# 01_-_CC2650.net
KiCad netlist of a schematic drawn in Altium Designer
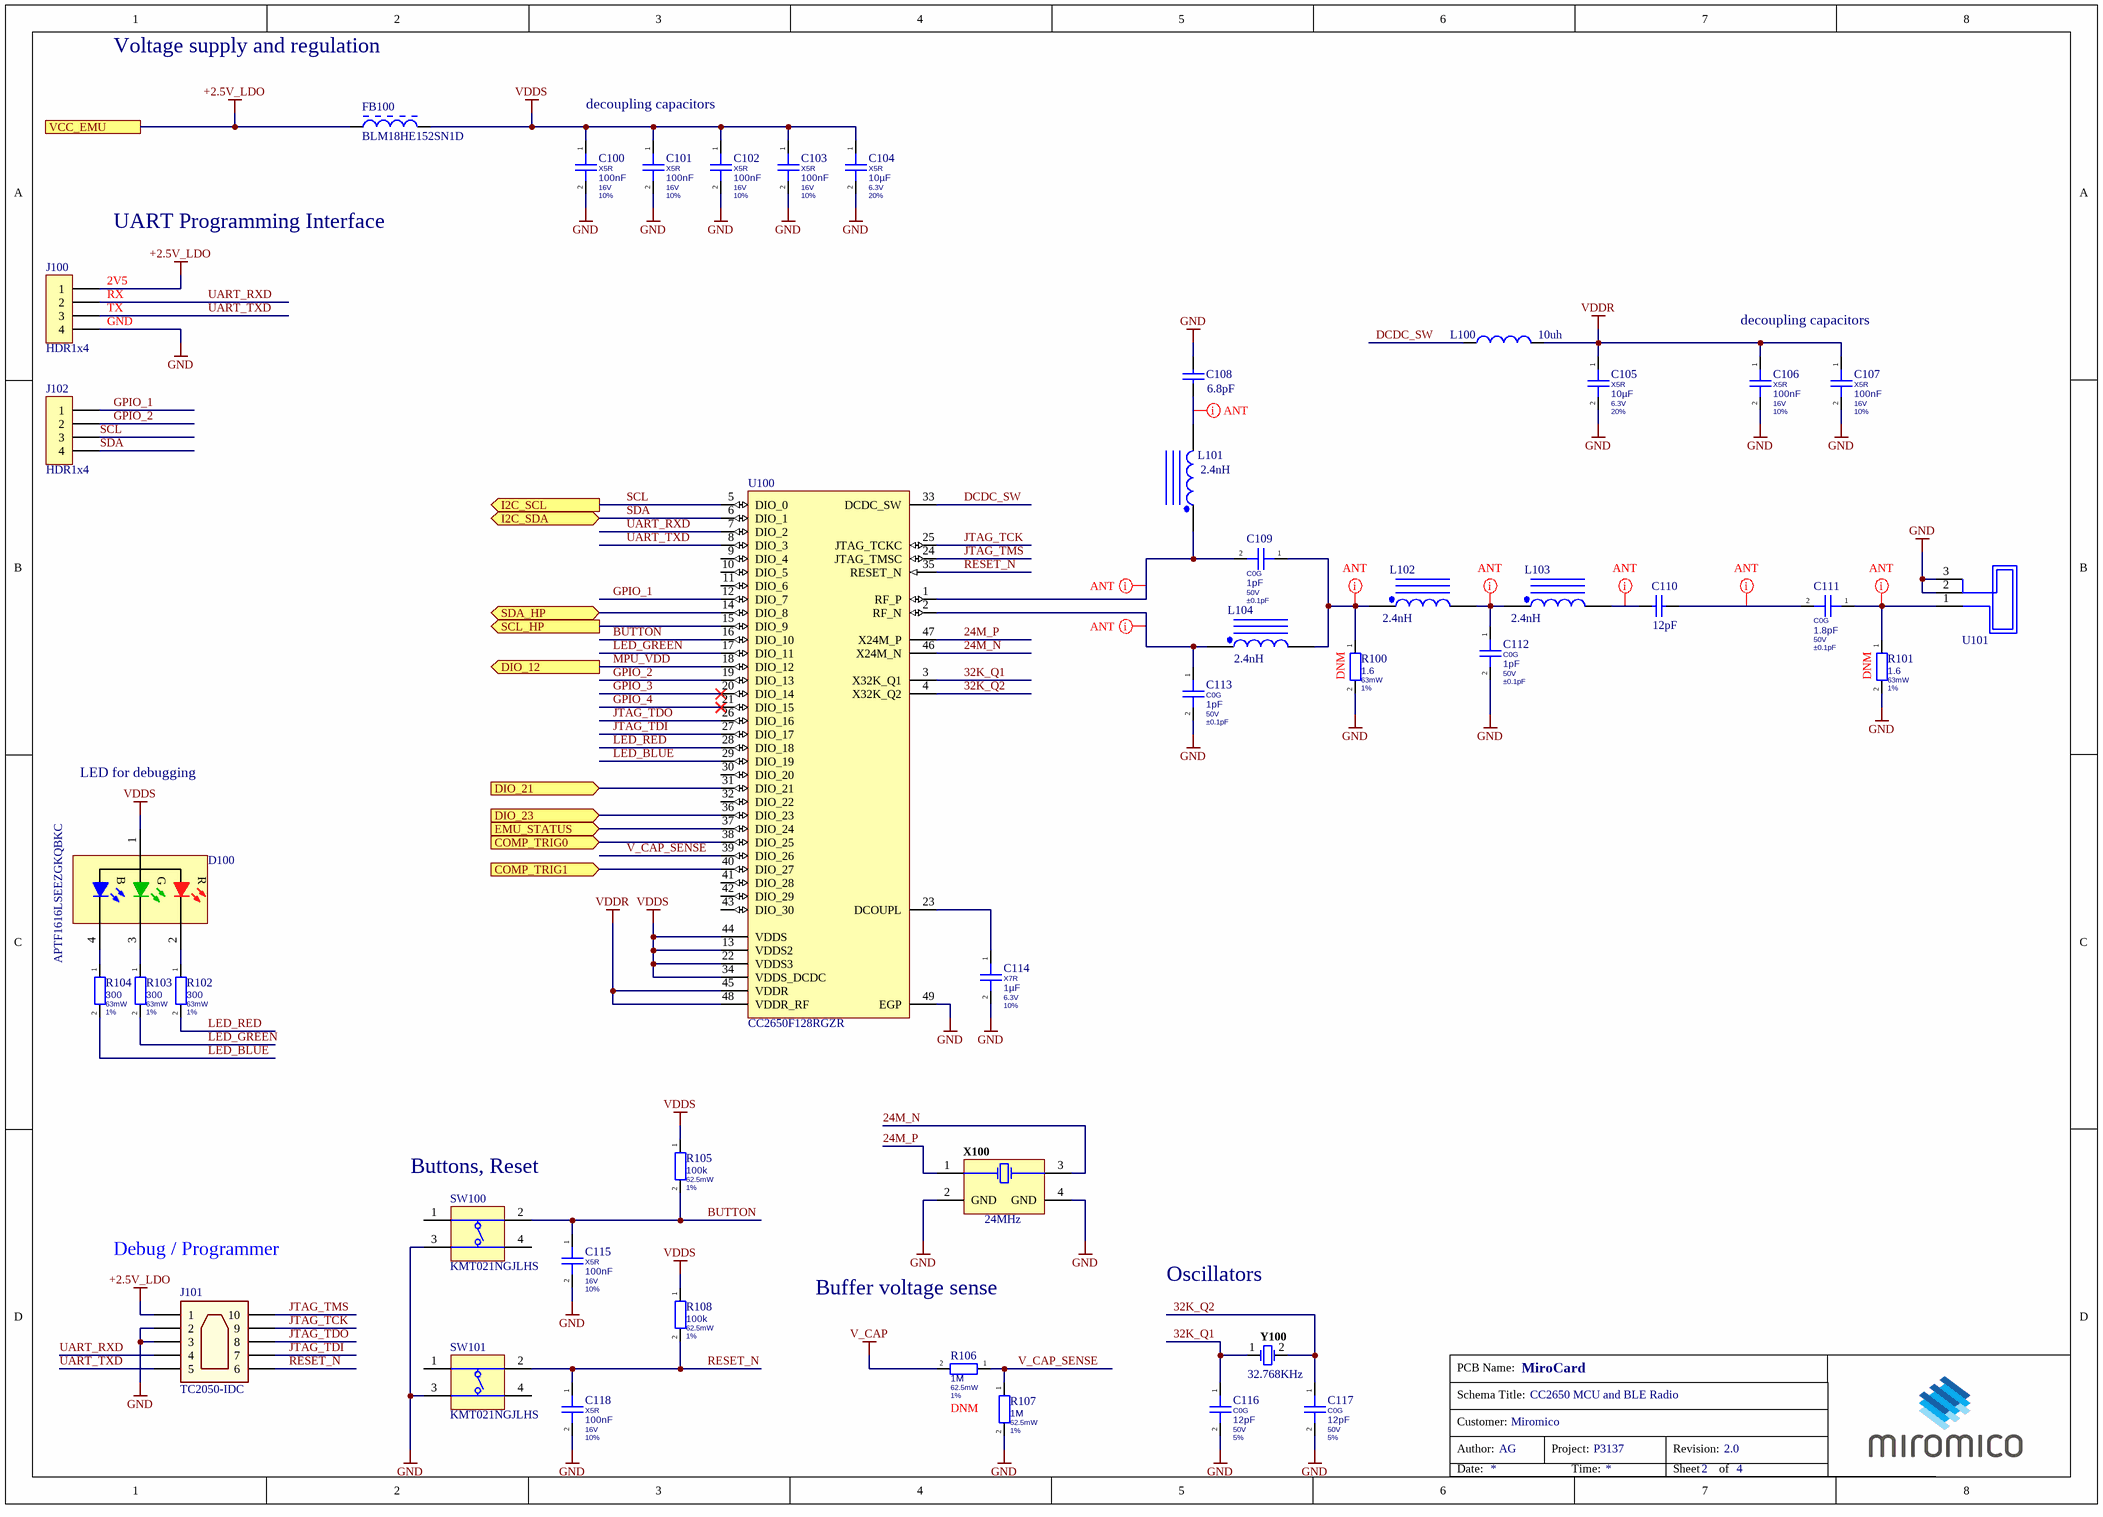
[diagram p0: 01 - CC2650.SchDoc]

(export (version "E")
  (design (tool "Eeschema 10.0.6"))
  (components
    (comp (ref "C100")
      (value "GRM155R61C104KA88D")
      (footprint "CAPC0402(1005)60_L")
      (description "0.1µF ±10% 16V Ceramic Capacitor X5R 0402 (1005 Metric)")
      (fields
        (field (name "DIELECTRIC") "X5R")
        (field (name "CAPACITANCE") "100nF")
        (field (name "VOLTAGE RATING") "16V")
        (field (name "TOLERANCE") "10%")
        (field (name "MANUFACTURER") "Murata Electronics")
        (field (name "VOLTAGE") "16V")
      )
      (libsource (lib "Altium Vault Miromico") (part "=Capacitance"))
    )
    (comp (ref "C101")
      (value "GRM155R61C104KA88D")
      (footprint "CAPC0402(1005)60_L")
      (description "0.1µF ±10% 16V Ceramic Capacitor X5R 0402 (1005 Metric)")
      (fields
        (field (name "DIELECTRIC") "X5R")
        (field (name "CAPACITANCE") "100nF")
        (field (name "VOLTAGE RATING") "16V")
        (field (name "TOLERANCE") "10%")
        (field (name "MANUFACTURER") "Murata Electronics")
        (field (name "VOLTAGE") "16V")
      )
      (libsource (lib "Altium Vault Miromico") (part "=Capacitance"))
    )
    (comp (ref "C102")
      (value "GRM155R61C104KA88D")
      (footprint "CAPC0402(1005)60_L")
      (description "0.1µF ±10% 16V Ceramic Capacitor X5R 0402 (1005 Metric)")
      (fields
        (field (name "DIELECTRIC") "X5R")
        (field (name "CAPACITANCE") "100nF")
        (field (name "VOLTAGE RATING") "16V")
        (field (name "TOLERANCE") "10%")
        (field (name "MANUFACTURER") "Murata Electronics")
        (field (name "VOLTAGE") "16V")
      )
      (libsource (lib "Altium Vault Miromico") (part "=Capacitance"))
    )
    (comp (ref "C103")
      (value "GRM155R61C104KA88D")
      (footprint "CAPC0402(1005)60_L")
      (description "0.1µF ±10% 16V Ceramic Capacitor X5R 0402 (1005 Metric)")
      (fields
        (field (name "DIELECTRIC") "X5R")
        (field (name "CAPACITANCE") "100nF")
        (field (name "VOLTAGE RATING") "16V")
        (field (name "TOLERANCE") "10%")
        (field (name "MANUFACTURER") "Murata Electronics")
        (field (name "VOLTAGE") "16V")
      )
      (libsource (lib "Altium Vault Miromico") (part "=Capacitance"))
    )
    (comp (ref "C104")
      (value "GRJ155R60J106ME11D")
      (footprint "CAPC0402(1005)60_L")
      (description "10µF ±20% 6.3V Ceramic Capacitor X5R 0402 (1005 Metric)")
      (fields
        (field (name "DIELECTRIC") "X5R")
        (field (name "CAPACITANCE") "10µF")
        (field (name "VOLTAGE RATING") "6.3V")
        (field (name "TOLERANCE") "20%")
        (field (name "MANUFACTURER") "Murata Electronics")
      )
      (libsource (lib "Altium Vault Miromico") (part "=Capacitance"))
    )
    (comp (ref "C105")
      (value "GRJ155R60J106ME11D")
      (footprint "CAPC0402(1005)60_L")
      (description "10µF ±20% 6.3V Ceramic Capacitor X5R 0402 (1005 Metric)")
      (fields
        (field (name "DIELECTRIC") "X5R")
        (field (name "CAPACITANCE") "10µF")
        (field (name "VOLTAGE RATING") "6.3V")
        (field (name "TOLERANCE") "20%")
        (field (name "MANUFACTURER") "Murata Electronics")
      )
      (libsource (lib "Altium Vault Miromico") (part "=Capacitance"))
    )
    (comp (ref "C106")
      (value "GRM155R61C104KA88D")
      (footprint "CAPC0402(1005)60_L")
      (description "0.1µF ±10% 16V Ceramic Capacitor X5R 0402 (1005 Metric)")
      (fields
        (field (name "DIELECTRIC") "X5R")
        (field (name "CAPACITANCE") "100nF")
        (field (name "VOLTAGE RATING") "16V")
        (field (name "TOLERANCE") "10%")
        (field (name "MANUFACTURER") "Murata Electronics")
        (field (name "VOLTAGE") "16V")
      )
      (libsource (lib "Altium Vault Miromico") (part "=Capacitance"))
    )
    (comp (ref "C107")
      (value "GRM155R61C104KA88D")
      (footprint "CAPC0402(1005)60_L")
      (description "0.1µF ±10% 16V Ceramic Capacitor X5R 0402 (1005 Metric)")
      (fields
        (field (name "DIELECTRIC") "X5R")
        (field (name "CAPACITANCE") "100nF")
        (field (name "VOLTAGE RATING") "16V")
        (field (name "TOLERANCE") "10%")
        (field (name "MANUFACTURER") "Murata Electronics")
        (field (name "VOLTAGE") "16V")
      )
      (libsource (lib "Altium Vault Miromico") (part "=Capacitance"))
    )
    (comp (ref "C108")
      (value "6.8pF")
      (footprint "CAPC0402(1005)60_L")
      (description "CAP 6.8pF 10V ±5% 0402 (1005 Metric) Thickness 0.6mm SMD")
      (fields (field (name "TOLERANCE") "Â±5%") (field (name "Comment") "CAP 6.8pF 10V 0402(1005)"))
      (libsource (lib "Altium Content Vault") (part "CMP-1034-00503-1"))
    )
    (comp (ref "C109")
      (value "GRM1555C1H1R0BA01D")
      (footprint "CAPC0402(1005)60_L")
      (description "1pF ±0.1pF 50V Ceramic Capacitor C0G, NP0 0402 (1005 Metric)")
      (fields
        (field (name "DIELECTRIC") "C0G")
        (field (name "CAPACITANCE") "1pF")
        (field (name "VOLTAGE RATING") "50V")
        (field (name "TOLERANCE") "±0.1pF")
        (field (name "MANUFACTURER") "Murata Electronics")
        (field (name "VOLTAGE") "50V")
      )
      (libsource (lib "Altium Vault Miromico") (part "=Capacitance"))
    )
    (comp (ref "C110")
      (value "12pF")
      (footprint "CAPC0402(1005)60_L")
      (description "CAP 12pF 10V ±2% 0402 (1005 Metric) Thickness 0.6mm SMD")
      (fields (field (name "TOLERANCE") "Â±2%") (field (name "Comment") "CAP 12pF 10V 0402(1005)"))
      (libsource (lib "Altium Content Vault") (part "CMP-1034-00750-1"))
    )
    (comp (ref "C111")
      (value "GRM1555C1H1R8BA01D")
      (footprint "CAPC0402(1005)60_L")
      (description "1.8pF ±0.1pF 50V Ceramic Capacitor C0G, NP0 0402 (1005 Metric)")
      (fields
        (field (name "DIELECTRIC") "C0G")
        (field (name "CAPACITANCE") "1.8pF")
        (field (name "VOLTAGE RATING") "50V")
        (field (name "TOLERANCE") "±0.1pF")
        (field (name "VOLTAGE") "50V")
        (field (name "MANUFACTURER") "Murata Electronics")
      )
      (libsource (lib "Altium Vault Miromico") (part "=Capacitance"))
    )
    (comp (ref "C112")
      (value "GRM1555C1H1R0BA01D")
      (footprint "CAPC0402(1005)60_L")
      (description "1pF ±0.1pF 50V Ceramic Capacitor C0G, NP0 0402 (1005 Metric)")
      (fields
        (field (name "DIELECTRIC") "C0G")
        (field (name "CAPACITANCE") "1pF")
        (field (name "VOLTAGE RATING") "50V")
        (field (name "TOLERANCE") "±0.1pF")
        (field (name "MANUFACTURER") "Murata Electronics")
        (field (name "VOLTAGE") "50V")
      )
      (libsource (lib "Altium Vault Miromico") (part "=Capacitance"))
    )
    (comp (ref "C113")
      (value "GRM1555C1H1R0BA01D")
      (footprint "CAPC0402(1005)60_L")
      (description "1pF ±0.1pF 50V Ceramic Capacitor C0G, NP0 0402 (1005 Metric)")
      (fields
        (field (name "DIELECTRIC") "C0G")
        (field (name "CAPACITANCE") "1pF")
        (field (name "VOLTAGE RATING") "50V")
        (field (name "TOLERANCE") "±0.1pF")
        (field (name "MANUFACTURER") "Murata Electronics")
        (field (name "VOLTAGE") "50V")
      )
      (libsource (lib "Altium Vault Miromico") (part "=Capacitance"))
    )
    (comp (ref "C114")
      (value "GRM155R70J105KA12J")
      (footprint "CAPC0402(1005)60_L")
      (description "1µF ±10% 6.3V Ceramic Capacitor X7R 0402 (1005 Metric)")
      (fields
        (field (name "DIELECTRIC") "X7R")
        (field (name "CAPACITANCE") "1µF")
        (field (name "VOLTAGE RATING") "6.3V")
        (field (name "TOLERANCE") "10%")
        (field (name "MANUFACTURER") "Murata Electronics")
      )
      (libsource (lib "Altium Vault Miromico") (part "=Capacitance"))
    )
    (comp (ref "C115")
      (value "GRM155R61C104KA88D")
      (footprint "CAPC0402(1005)60_L")
      (description "0.1µF ±10% 16V Ceramic Capacitor X5R 0402 (1005 Metric)")
      (fields
        (field (name "DIELECTRIC") "X5R")
        (field (name "CAPACITANCE") "100nF")
        (field (name "VOLTAGE RATING") "16V")
        (field (name "TOLERANCE") "10%")
        (field (name "MANUFACTURER") "Murata Electronics")
        (field (name "VOLTAGE") "16V")
      )
      (libsource (lib "Altium Vault Miromico") (part "=Capacitance"))
    )
    (comp (ref "C116")
      (value "GRM1555C1H120JA01D")
      (footprint "CAPC0402(1005)60_L")
      (description "12pF ±5% 50V Ceramic Capacitor C0G, NP0 0402 (1005 Metric)")
      (fields
        (field (name "DIELECTRIC") "C0G")
        (field (name "CAPACITANCE") "12pF")
        (field (name "VOLTAGE RATING") "50V")
        (field (name "TOLERANCE") "5%")
        (field (name "MANUFACTURER") "Murata Electronics")
        (field (name "VOLTAGE") "50V")
      )
      (libsource (lib "Altium Vault Miromico") (part "=Capacitance"))
    )
    (comp (ref "C117")
      (value "GRM1555C1H120JA01D")
      (footprint "CAPC0402(1005)60_L")
      (description "12pF ±5% 50V Ceramic Capacitor C0G, NP0 0402 (1005 Metric)")
      (fields
        (field (name "DIELECTRIC") "C0G")
        (field (name "CAPACITANCE") "12pF")
        (field (name "VOLTAGE RATING") "50V")
        (field (name "TOLERANCE") "5%")
        (field (name "MANUFACTURER") "Murata Electronics")
        (field (name "VOLTAGE") "50V")
      )
      (libsource (lib "Altium Vault Miromico") (part "=Capacitance"))
    )
    (comp (ref "C118")
      (value "GRM155R61C104KA88D")
      (footprint "CAPC0402(1005)60_L")
      (description "0.1µF ±10% 16V Ceramic Capacitor X5R 0402 (1005 Metric)")
      (fields
        (field (name "DIELECTRIC") "X5R")
        (field (name "CAPACITANCE") "100nF")
        (field (name "VOLTAGE RATING") "16V")
        (field (name "TOLERANCE") "10%")
        (field (name "MANUFACTURER") "Murata Electronics")
        (field (name "VOLTAGE") "16V")
      )
      (libsource (lib "Altium Vault Miromico") (part "=Capacitance"))
    )
    (comp (ref "D100")
      (value "APTF1616LSEEZGKQBKC")
      (footprint "APTF1616LSEEZGKQBKC")
      (description "HELI Colour; 1.6X1.6MM LOW CURRENT RGB SMD LED")
      (fields (field (name "MANUFACTURER") "Kingbright"))
      (libsource (lib "Altium Vault Miromico") (part "APTF1616LSEEZGKQBKC"))
    )
    (comp (ref "FB100")
      (value "BLM18HE152SN1D")
      (footprint "MURA-BLM18-RF-H4-CHIP-2_V")
      (fields (field (name "MANUFACTURER") "Murata"))
      (libsource (lib "Altium Content Vault") (part "MURA-FB-2"))
    )
    (comp (ref "J100")
      (value "HDR1x4")
      (footprint "HDR1x4")
      (description "1x4 Pin Header, 2.54mm")
      (libsource (lib "Altium Vault Miromico") (part "HDR1x4"))
    )
    (comp (ref "J101")
      (value "TC2050-IDC")
      (footprint "TC2050-IDC-NL-10")
      (description "TDC2050-IDC, 10Pins, dual footprint (leg and no-legs)")
      (fields (field (name "MANUFACTURER") "Tag-Connect"))
      (libsource (lib "Altium Vault Miromico") (part "TDC2050-IDC-03"))
    )
    (comp (ref "J102")
      (value "HDR1x4")
      (footprint "HDR1x4")
      (description "1x4 Pin Header, 2.54mm")
      (libsource (lib "Altium Vault Miromico") (part "HDR1x4"))
    )
    (comp (ref "L100")
      (value "CKS2125100M-T")
      (footprint "INDC0805(2012)X11_L")
      (description "FIXED IND 10UH 110MA 520 MOHM")
      (fields (field (name "TOLERANCE") "20%") (field (name "INDUCTANCE") "10uh"))
      (libsource (lib "TransientBLE") (part "CMP-00871-1"))
    )
    (comp (ref "L101")
      (value "LQG15HS2N4S02D")
      (footprint "INDC1005X55X25LL05T10_A")
      (fields
        (field (name "INDUCTANCE") "2.4nH")
        (field (name "MANUFACTURER") "MurataElectronics")
        (field (name "TOLERANCE") "0.3nH")
      )
      (libsource (lib "Altium Content Vault") (part "CMP-2000-06579-1"))
    )
    (comp (ref "L102")
      (value "LQG15HS2N4S02D")
      (footprint "INDC1005X55X25LL05T10_A")
      (fields
        (field (name "INDUCTANCE") "2.4nH")
        (field (name "MANUFACTURER") "MurataElectronics")
        (field (name "TOLERANCE") "0.3nH")
      )
      (libsource (lib "Altium Content Vault") (part "CMP-2000-06579-1"))
    )
    (comp (ref "L103")
      (value "LQG15HS2N4S02D")
      (footprint "INDC1005X55X25LL05T10_A")
      (fields
        (field (name "INDUCTANCE") "2.4nH")
        (field (name "MANUFACTURER") "MurataElectronics")
        (field (name "TOLERANCE") "0.3nH")
      )
      (libsource (lib "Altium Content Vault") (part "CMP-2000-06579-1"))
    )
    (comp (ref "L104")
      (value "LQG15HS2N4S02D")
      (footprint "INDC1005X55X25LL05T10_A")
      (fields
        (field (name "INDUCTANCE") "2.4nH")
        (field (name "MANUFACTURER") "MurataElectronics")
        (field (name "TOLERANCE") "0.3nH")
      )
      (libsource (lib "Altium Content Vault") (part "CMP-2000-06579-1"))
    )
    (comp (ref "R100")
      (value "CRCW04021R60FKED")
      (footprint "RESC0402(1005)_L")
      (description "1.6 Ohms ±1% 0.063W, 1/16W Chip Resistor 0402 (1005 Metric) Automotive AEC-Q200 Thick Film")
      (fields
        (field (name "RESISTANCE") "1.6")
        (field (name "POWER RATING") "63mW")
        (field (name "TOLERANCE") "1%")
        (field (name "MANUFACTURER") "Vishay Dale")
      )
      (libsource (lib "") (part "=Resistance_1"))
    )
    (comp (ref "R101")
      (value "CRCW04021R60FKED")
      (footprint "RESC0402(1005)_L")
      (description "1.6 Ohms ±1% 0.063W, 1/16W Chip Resistor 0402 (1005 Metric) Automotive AEC-Q200 Thick Film")
      (fields
        (field (name "RESISTANCE") "1.6")
        (field (name "POWER RATING") "63mW")
        (field (name "TOLERANCE") "1%")
        (field (name "MANUFACTURER") "Vishay Dale")
      )
      (libsource (lib "") (part "=Resistance_1"))
    )
    (comp (ref "R102")
      (value "RMCF0402FT300R")
      (footprint "RESC0402(1005)_L")
      (fields
        (field (name "RESISTANCE") "300")
        (field (name "POWER RATING") "63mW")
        (field (name "TOLERANCE") "1%")
        (field (name "MANUFACTURER") "Stackpole Electronics Inc")
      )
      (libsource (lib "") (part "=Resistance_1"))
    )
    (comp (ref "R103")
      (value "RMCF0402FT300R")
      (footprint "RESC0402(1005)_L")
      (fields
        (field (name "RESISTANCE") "300")
        (field (name "POWER RATING") "63mW")
        (field (name "TOLERANCE") "1%")
        (field (name "MANUFACTURER") "Stackpole Electronics Inc")
      )
      (libsource (lib "") (part "=Resistance_1"))
    )
    (comp (ref "R104")
      (value "RMCF0402FT300R")
      (footprint "RESC0402(1005)_L")
      (fields
        (field (name "RESISTANCE") "300")
        (field (name "POWER RATING") "63mW")
        (field (name "TOLERANCE") "1%")
        (field (name "MANUFACTURER") "Stackpole Electronics Inc")
      )
      (libsource (lib "") (part "=Resistance_1"))
    )
    (comp (ref "R105")
      (value "RMCF0402FT100K")
      (footprint "RESC0402(1005)_L")
      (fields
        (field (name "RESISTANCE") "100k")
        (field (name "POWER RATING") "62.5mW")
        (field (name "TOLERANCE") "1%")
        (field (name "MANUFACTURER") "Stackpole Electronics Inc")
      )
      (libsource (lib "") (part "=Resistance_1"))
    )
    (comp (ref "R106")
      (value "RMCF0402FT1M00")
      (footprint "RESC0402(1005)_L")
      (fields
        (field (name "RESISTANCE") "1M")
        (field (name "POWER RATING") "62.5mW")
        (field (name "TOLERANCE") "1%")
        (field (name "MANUFACTURER") "Stackpole Electronics Inc")
      )
      (libsource (lib "Altium Vault Miromico") (part "=Resistance"))
    )
    (comp (ref "R107")
      (value "RMCF0402FT1M00")
      (footprint "RESC0402(1005)_L")
      (fields
        (field (name "RESISTANCE") "1M")
        (field (name "POWER RATING") "62.5mW")
        (field (name "TOLERANCE") "1%")
        (field (name "MANUFACTURER") "Stackpole Electronics Inc")
      )
      (libsource (lib "") (part "=Resistance_1"))
    )
    (comp (ref "R108")
      (value "RMCF0402FT100K")
      (footprint "RESC0402(1005)_L")
      (fields
        (field (name "RESISTANCE") "100k")
        (field (name "POWER RATING") "62.5mW")
        (field (name "TOLERANCE") "1%")
        (field (name "MANUFACTURER") "Stackpole Electronics Inc")
      )
      (libsource (lib "") (part "=Resistance_1"))
    )
    (comp (ref "SW100")
      (value "KMT021NGJLHS")
      (footprint "KMT021NGJLHS-Footprint-1")
      (description "Sensorschalter Ultra-LW Tact SW SMT SPNOFa 1.6N HF")
      (fields (field (name "MANUFACTURER") "C&K"))
      (libsource (lib "Altium Vault Miromico") (part "KMT021NGJLHS"))
    )
    (comp (ref "SW101")
      (value "KMT021NGJLHS")
      (footprint "KMT021NGJLHS-Footprint-1")
      (description "Sensorschalter Ultra-LW Tact SW SMT SPNOFa 1.6N HF")
      (fields (field (name "MANUFACTURER") "C&K"))
      (libsource (lib "Altium Vault Miromico") (part "KMT021NGJLHS"))
    )
    (comp (ref "U100")
      (value "CC2650F128RGZR")
      (footprint "RGZ0048A_V")
      (fields (field (name "MANUFACTURER") "Texas Instruments"))
      (libsource (lib "Altium Content Vault") (part "TI-CC2650-VFQFN-48"))
    )
    (comp (ref "U101")
      (value "Antenna Patch")
      (footprint "2.4GHz Inverted F Antenna")
      (description "2.4GHz Inverted F Antenna")
      (libsource (lib "TransientBLE") (part "CMP-00262-1"))
    )
    (comp (ref "X100")
      (value "TSX-3225 24.0000MF15X-AC3")
      (footprint "EPSON-TSX-3225_V")
      (description "MHz Range Crystal, 24 MHz, -40 to 85 degC, 4-Pin SMD, RoHS, Tape and Reel")
      (fields
        (field (name "TOLERANCE") "10PPM")
        (field (name "FREQUENCY") "24MHz")
        (field (name "MANUFACTURER") "Epson")
      )
      (libsource (lib "Altium Content Vault") (part "CMP-2000-07333-1"))
    )
    (comp (ref "Y100")
      (value "ABS07-120-32.768KHZ-T")
      (footprint "ABRA-ABS07_A_V")
      (description "Tuning Fork Crystal, 32.768 KHz, +/- 20 ppm, -40 to 85 degC, 2-Pin SMD, RoHS, Tape and Reel")
      (fields
        (field (name "FREQUENCY") "32.768KHz")
        (field (name "MANUFACTURER") "Abracon")
        (field (name "TOLERANCE") "20ppm")
      )
      (libsource (lib "Altium Content Vault") (part "CMP-2000-07587-1"))
    )
  )
  (nets
    (net (code "1") (name "+2.5V_LDO") (class "Default")
      (node (ref "FB100") (pin "1") (pinfunction "1_1") (pintype "passive"))
      (node (ref "J100") (pin "1") (pinfunction "1_1") (pintype "passive"))
      (node (ref "J101") (pin "1") (pinfunction "1_1") (pintype "passive"))
    )
    (net (code "2") (name "/24M_N") (class "Default")
      (node (ref "U100") (pin "46") (pinfunction "X24M_N_46") (pintype "passive"))
      (node (ref "X100") (pin "3") (pinfunction "X2_3") (pintype "passive"))
    )
    (net (code "3") (name "/24M_P") (class "Default")
      (node (ref "U100") (pin "47") (pinfunction "X24M_P_47") (pintype "passive"))
      (node (ref "X100") (pin "1") (pinfunction "X1_1") (pintype "passive"))
    )
    (net (code "4") (name "/32K_Q1") (class "Default")
      (node (ref "C116") (pin "1") (pinfunction "1_1") (pintype "passive"))
      (node (ref "U100") (pin "3") (pinfunction "X32K_Q1_3") (pintype "passive"))
      (node (ref "Y100") (pin "1") (pinfunction "1_1") (pintype "passive"))
    )
    (net (code "5") (name "/32K_Q2") (class "Default")
      (node (ref "C117") (pin "1") (pinfunction "1_1") (pintype "passive"))
      (node (ref "U100") (pin "4") (pinfunction "X32K_Q2_4") (pintype "passive"))
      (node (ref "Y100") (pin "2") (pinfunction "2_2") (pintype "passive"))
    )
    (net (code "6") (name "/BUTTON") (class "Default")
      (node (ref "C115") (pin "1") (pinfunction "1_1") (pintype "passive"))
      (node (ref "R105") (pin "2") (pinfunction "2_2") (pintype "passive"))
      (node (ref "SW100") (pin "2") (pinfunction "T2_2") (pintype "passive"))
      (node (ref "U100") (pin "16") (pinfunction "DIO_10_16") (pintype "bidirectional"))
    )
    (net (code "7") (name "/COMP_TRIG0") (class "Default")
      (node (ref "U100") (pin "38") (pinfunction "DIO_25_38") (pintype "bidirectional"))
    )
    (net (code "8") (name "/COMP_TRIG1") (class "Default")
      (node (ref "U100") (pin "40") (pinfunction "DIO_27_40") (pintype "bidirectional"))
    )
    (net (code "9") (name "/DCDC_SW") (class "Default")
      (node (ref "L100") (pin "1") (pinfunction "1_1") (pintype "passive"))
      (node (ref "U100") (pin "33") (pinfunction "DCDC_SW_33") (pintype "power_in"))
    )
    (net (code "10") (name "/DIO_21") (class "Default")
      (node (ref "U100") (pin "31") (pinfunction "DIO_21_31") (pintype "bidirectional"))
    )
    (net (code "11") (name "/DIO_23") (class "Default")
      (node (ref "U100") (pin "36") (pinfunction "DIO_23_36") (pintype "bidirectional"))
    )
    (net (code "12") (name "/EMU_STATUS") (class "Default")
      (node (ref "U100") (pin "37") (pinfunction "DIO_24_37") (pintype "bidirectional"))
    )
    (net (code "13") (name "/GPIO_1") (class "Default")
      (node (ref "J102") (pin "1") (pinfunction "1_1") (pintype "passive"))
      (node (ref "U100") (pin "12") (pinfunction "DIO_7_12") (pintype "bidirectional"))
    )
    (net (code "14") (name "/GPIO_2") (class "Default")
      (node (ref "J102") (pin "2") (pinfunction "2_2") (pintype "passive"))
      (node (ref "U100") (pin "19") (pinfunction "DIO_13_19") (pintype "bidirectional"))
    )
    (net (code "15") (name "/GPIO_3") (class "Default")
      (node (ref "U100") (pin "20") (pinfunction "DIO_14_20") (pintype "bidirectional+no_connect"))
    )
    (net (code "16") (name "/GPIO_4") (class "Default")
      (node (ref "U100") (pin "21") (pinfunction "DIO_15_21") (pintype "bidirectional+no_connect"))
    )
    (net (code "17") (name "/JTAG_TCK") (class "Default")
      (node (ref "J101") (pin "9") (pinfunction "9_9") (pintype "passive"))
      (node (ref "U100") (pin "25") (pinfunction "JTAG_TCKC_25") (pintype "bidirectional"))
    )
    (net (code "18") (name "/JTAG_TDI") (class "Default")
      (node (ref "J101") (pin "7") (pinfunction "7_7") (pintype "passive"))
      (node (ref "U100") (pin "27") (pinfunction "DIO_17_27") (pintype "bidirectional"))
    )
    (net (code "19") (name "/JTAG_TDO") (class "Default")
      (node (ref "J101") (pin "8") (pinfunction "8_8") (pintype "passive"))
      (node (ref "U100") (pin "26") (pinfunction "DIO_16_26") (pintype "bidirectional"))
    )
    (net (code "20") (name "/JTAG_TMS") (class "Default")
      (node (ref "J101") (pin "10") (pinfunction "10_10") (pintype "passive"))
      (node (ref "U100") (pin "24") (pinfunction "JTAG_TMSC_24") (pintype "bidirectional"))
    )
    (net (code "21") (name "/LED_BLUE") (class "Default")
      (node (ref "R104") (pin "2") (pinfunction "2_2") (pintype "passive"))
      (node (ref "U100") (pin "29") (pinfunction "DIO_19_29") (pintype "bidirectional"))
    )
    (net (code "22") (name "/LED_GREEN") (class "Default")
      (node (ref "R103") (pin "2") (pinfunction "2_2") (pintype "passive"))
      (node (ref "U100") (pin "17") (pinfunction "DIO_11_17") (pintype "bidirectional"))
    )
    (net (code "23") (name "/LED_RED") (class "Default")
      (node (ref "R102") (pin "2") (pinfunction "2_2") (pintype "passive"))
      (node (ref "U100") (pin "28") (pinfunction "DIO_18_28") (pintype "bidirectional"))
    )
    (net (code "24") (name "/MPU_VDD") (class "Default")
      (node (ref "U100") (pin "18") (pinfunction "DIO_12_18") (pintype "bidirectional"))
    )
    (net (code "25") (name "/RESET_N") (class "Default")
      (node (ref "C118") (pin "1") (pinfunction "1_1") (pintype "passive"))
      (node (ref "J101") (pin "6") (pinfunction "6_6") (pintype "passive"))
      (node (ref "R108") (pin "2") (pinfunction "2_2") (pintype "passive"))
      (node (ref "SW101") (pin "2") (pinfunction "T2_2") (pintype "passive"))
      (node (ref "U100") (pin "35") (pinfunction "RESET_N_35") (pintype "input"))
    )
    (net (code "26") (name "/SCL") (class "Default")
      (node (ref "J102") (pin "3") (pinfunction "3_3") (pintype "passive"))
      (node (ref "U100") (pin "5") (pinfunction "DIO_0_5") (pintype "bidirectional"))
    )
    (net (code "27") (name "/SCL_HP") (class "Default")
      (node (ref "U100") (pin "15") (pinfunction "DIO_9_15") (pintype "bidirectional"))
    )
    (net (code "28") (name "/SDA") (class "Default")
      (node (ref "J102") (pin "4") (pinfunction "4_4") (pintype "passive"))
      (node (ref "U100") (pin "6") (pinfunction "DIO_1_6") (pintype "bidirectional"))
    )
    (net (code "29") (name "/SDA_HP") (class "Default")
      (node (ref "U100") (pin "14") (pinfunction "DIO_8_14") (pintype "bidirectional"))
    )
    (net (code "30") (name "/UART_RXD") (class "Default")
      (node (ref "J100") (pin "2") (pinfunction "2_2") (pintype "passive"))
      (node (ref "J101") (pin "4") (pinfunction "4_4") (pintype "passive"))
      (node (ref "U100") (pin "7") (pinfunction "DIO_2_7") (pintype "bidirectional"))
    )
    (net (code "31") (name "/UART_TXD") (class "Default")
      (node (ref "J100") (pin "3") (pinfunction "3_3") (pintype "passive"))
      (node (ref "J101") (pin "5") (pinfunction "5_5") (pintype "passive"))
      (node (ref "U100") (pin "8") (pinfunction "DIO_3_8") (pintype "bidirectional"))
    )
    (net (code "32") (name "/V_CAP_SENSE") (class "Default")
      (node (ref "R106") (pin "1") (pinfunction "1_1") (pintype "passive"))
      (node (ref "R107") (pin "1") (pinfunction "1_1") (pintype "passive"))
      (node (ref "U100") (pin "39") (pinfunction "DIO_26_39") (pintype "bidirectional"))
    )
    (net (code "33") (name "GND") (class "Default")
      (node (ref "C100") (pin "2") (pinfunction "2_2") (pintype "passive"))
      (node (ref "C101") (pin "2") (pinfunction "2_2") (pintype "passive"))
      (node (ref "C102") (pin "2") (pinfunction "2_2") (pintype "passive"))
      (node (ref "C103") (pin "2") (pinfunction "2_2") (pintype "passive"))
      (node (ref "C104") (pin "2") (pinfunction "2_2") (pintype "passive"))
      (node (ref "C105") (pin "2") (pinfunction "2_2") (pintype "passive"))
      (node (ref "C106") (pin "2") (pinfunction "2_2") (pintype "passive"))
      (node (ref "C107") (pin "2") (pinfunction "2_2") (pintype "passive"))
      (node (ref "C108") (pin "2") (pinfunction "2_2") (pintype "passive"))
      (node (ref "C112") (pin "2") (pinfunction "2_2") (pintype "passive"))
      (node (ref "C113") (pin "2") (pinfunction "2_2") (pintype "passive"))
      (node (ref "C114") (pin "2") (pinfunction "2_2") (pintype "passive"))
      (node (ref "C115") (pin "2") (pinfunction "2_2") (pintype "passive"))
      (node (ref "C116") (pin "2") (pinfunction "2_2") (pintype "passive"))
      (node (ref "C117") (pin "2") (pinfunction "2_2") (pintype "passive"))
      (node (ref "C118") (pin "2") (pinfunction "2_2") (pintype "passive"))
      (node (ref "J100") (pin "4") (pinfunction "4_4") (pintype "passive"))
      (node (ref "J101") (pin "2") (pinfunction "2_2") (pintype "passive"))
      (node (ref "J101") (pin "3") (pinfunction "3_3") (pintype "passive"))
      (node (ref "R100") (pin "2") (pinfunction "2_2") (pintype "passive"))
      (node (ref "R101") (pin "2") (pinfunction "2_2") (pintype "passive"))
      (node (ref "R107") (pin "2") (pinfunction "2_2") (pintype "passive"))
      (node (ref "SW100") (pin "3") (pinfunction "T3_3") (pintype "passive"))
      (node (ref "SW101") (pin "3") (pinfunction "T3_3") (pintype "passive"))
      (node (ref "U100") (pin "49") (pinfunction "EGP_49") (pintype "power_in"))
      (node (ref "U101") (pin "2") (pinfunction "2_2") (pintype "passive"))
      (node (ref "U101") (pin "3") (pinfunction "3_3") (pintype "passive"))
      (node (ref "X100") (pin "2") (pinfunction "GND_2") (pintype "power_in"))
      (node (ref "X100") (pin "4") (pinfunction "GND_4") (pintype "power_in"))
    )
    (net (code "34") (name "Net-(C108-Pad1)") (class "Default")
      (node (ref "C108") (pin "1") (pinfunction "1_1") (pintype "passive"))
      (node (ref "L101") (pin "2") (pinfunction "2_2") (pintype "passive"))
    )
    (net (code "35") (name "Net-(C109-Pad1)") (class "Default")
      (node (ref "C109") (pin "1") (pinfunction "1_1") (pintype "passive"))
      (node (ref "L102") (pin "1") (pinfunction "1_1") (pintype "passive"))
      (node (ref "L104") (pin "2") (pinfunction "2_2") (pintype "passive"))
      (node (ref "R100") (pin "1") (pinfunction "1_1") (pintype "passive"))
    )
    (net (code "36") (name "Net-(C110-Pad1)") (class "Default")
      (node (ref "C110") (pin "1") (pinfunction "1_1") (pintype "passive"))
      (node (ref "L103") (pin "2") (pinfunction "2_2") (pintype "passive"))
    )
    (net (code "37") (name "Net-(C110-Pad2)") (class "Default")
      (node (ref "C110") (pin "2") (pinfunction "2_2") (pintype "passive"))
      (node (ref "C111") (pin "2") (pinfunction "2_2") (pintype "passive"))
    )
    (net (code "38") (name "Net-(C111-Pad1)") (class "Default")
      (node (ref "C111") (pin "1") (pinfunction "1_1") (pintype "passive"))
      (node (ref "R101") (pin "1") (pinfunction "1_1") (pintype "passive"))
      (node (ref "U101") (pin "1") (pinfunction "1_1") (pintype "passive"))
    )
    (net (code "39") (name "Net-(C112-Pad1)") (class "Default")
      (node (ref "C112") (pin "1") (pinfunction "1_1") (pintype "passive"))
      (node (ref "L102") (pin "2") (pinfunction "2_2") (pintype "passive"))
      (node (ref "L103") (pin "1") (pinfunction "1_1") (pintype "passive"))
    )
    (net (code "40") (name "Net-(D100-B)") (class "Default")
      (node (ref "D100") (pin "4") (pinfunction "B_4") (pintype "passive"))
      (node (ref "R104") (pin "1") (pinfunction "1_1") (pintype "passive"))
    )
    (net (code "41") (name "Net-(D100-G)") (class "Default")
      (node (ref "D100") (pin "3") (pinfunction "G_3") (pintype "passive"))
      (node (ref "R103") (pin "1") (pinfunction "1_1") (pintype "passive"))
    )
    (net (code "42") (name "Net-(D100-R)") (class "Default")
      (node (ref "D100") (pin "2") (pinfunction "R_2") (pintype "passive"))
      (node (ref "R102") (pin "1") (pinfunction "1_1") (pintype "passive"))
    )
    (net (code "43") (name "Net-(U100-DCOUPL)") (class "Default")
      (node (ref "C114") (pin "1") (pinfunction "1_1") (pintype "passive"))
      (node (ref "U100") (pin "23") (pinfunction "DCOUPL_23") (pintype "passive"))
    )
    (net (code "44") (name "Net-(U100-RF_N)") (class "Default")
      (node (ref "C113") (pin "1") (pinfunction "1_1") (pintype "passive"))
      (node (ref "L104") (pin "1") (pinfunction "1_1") (pintype "passive"))
      (node (ref "U100") (pin "2") (pinfunction "RF_N_2") (pintype "bidirectional"))
    )
    (net (code "45") (name "Net-(U100-RF_P)") (class "Default")
      (node (ref "C109") (pin "2") (pinfunction "2_2") (pintype "passive"))
      (node (ref "L101") (pin "1") (pinfunction "1_1") (pintype "passive"))
      (node (ref "U100") (pin "1") (pinfunction "RF_P_1") (pintype "bidirectional"))
    )
    (net (code "46") (name "VDDR") (class "Default")
      (node (ref "C105") (pin "1") (pinfunction "1_1") (pintype "passive"))
      (node (ref "C106") (pin "1") (pinfunction "1_1") (pintype "passive"))
      (node (ref "C107") (pin "1") (pinfunction "1_1") (pintype "passive"))
      (node (ref "L100") (pin "2") (pinfunction "2_2") (pintype "passive"))
      (node (ref "U100") (pin "45") (pinfunction "VDDR_45") (pintype "power_in"))
      (node (ref "U100") (pin "48") (pinfunction "VDDR_RF_48") (pintype "power_in"))
    )
    (net (code "47") (name "VDDS") (class "Default")
      (node (ref "C100") (pin "1") (pinfunction "1_1") (pintype "passive"))
      (node (ref "C101") (pin "1") (pinfunction "1_1") (pintype "passive"))
      (node (ref "C102") (pin "1") (pinfunction "1_1") (pintype "passive"))
      (node (ref "C103") (pin "1") (pinfunction "1_1") (pintype "passive"))
      (node (ref "C104") (pin "1") (pinfunction "1_1") (pintype "passive"))
      (node (ref "D100") (pin "1") (pinfunction "1_1") (pintype "passive"))
      (node (ref "FB100") (pin "2") (pinfunction "2_2") (pintype "passive"))
      (node (ref "R105") (pin "1") (pinfunction "1_1") (pintype "passive"))
      (node (ref "R108") (pin "1") (pinfunction "1_1") (pintype "passive"))
      (node (ref "U100") (pin "13") (pinfunction "VDDS2_13") (pintype "power_in"))
      (node (ref "U100") (pin "22") (pinfunction "VDDS3_22") (pintype "power_in"))
      (node (ref "U100") (pin "34") (pinfunction "VDDS_DCDC_34") (pintype "power_in"))
      (node (ref "U100") (pin "44") (pinfunction "VDDS_44") (pintype "power_in"))
    )
    (net (code "48") (name "V_CAP") (class "Default")
      (node (ref "R106") (pin "2") (pinfunction "2_2") (pintype "passive"))
    )
    (net (code "49") (name "unconnected-(SW100-T1-Pad1)") (class "Default")
      (node (ref "SW100") (pin "1") (pinfunction "T1_1") (pintype "passive"))
    )
    (net (code "50") (name "unconnected-(SW100-T3-Pad4)") (class "Default")
      (node (ref "SW100") (pin "4") (pinfunction "T3_4") (pintype "passive"))
    )
    (net (code "51") (name "unconnected-(SW101-T1-Pad1)") (class "Default")
      (node (ref "SW101") (pin "1") (pinfunction "T1_1") (pintype "passive"))
    )
    (net (code "52") (name "unconnected-(SW101-T3-Pad4)") (class "Default")
      (node (ref "SW101") (pin "4") (pinfunction "T3_4") (pintype "passive"))
    )
    (net (code "53") (name "unconnected-(U100-DIO_4-Pad9)") (class "Default")
      (node (ref "U100") (pin "9") (pinfunction "DIO_4_9") (pintype "bidirectional"))
    )
    (net (code "54") (name "unconnected-(U100-DIO_5-Pad10)") (class "Default")
      (node (ref "U100") (pin "10") (pinfunction "DIO_5_10") (pintype "bidirectional"))
    )
    (net (code "55") (name "unconnected-(U100-DIO_6-Pad11)") (class "Default")
      (node (ref "U100") (pin "11") (pinfunction "DIO_6_11") (pintype "bidirectional"))
    )
    (net (code "56") (name "unconnected-(U100-DIO_20-Pad30)") (class "Default")
      (node (ref "U100") (pin "30") (pinfunction "DIO_20_30") (pintype "bidirectional"))
    )
    (net (code "57") (name "unconnected-(U100-DIO_22-Pad32)") (class "Default")
      (node (ref "U100") (pin "32") (pinfunction "DIO_22_32") (pintype "bidirectional"))
    )
    (net (code "58") (name "unconnected-(U100-DIO_28-Pad41)") (class "Default")
      (node (ref "U100") (pin "41") (pinfunction "DIO_28_41") (pintype "bidirectional"))
    )
    (net (code "59") (name "unconnected-(U100-DIO_29-Pad42)") (class "Default")
      (node (ref "U100") (pin "42") (pinfunction "DIO_29_42") (pintype "bidirectional"))
    )
    (net (code "60") (name "unconnected-(U100-DIO_30-Pad43)") (class "Default")
      (node (ref "U100") (pin "43") (pinfunction "DIO_30_43") (pintype "bidirectional"))
    )
  )
)
